# web_sch.net
KiCad netlist of a schematic drawn in Altium Designer
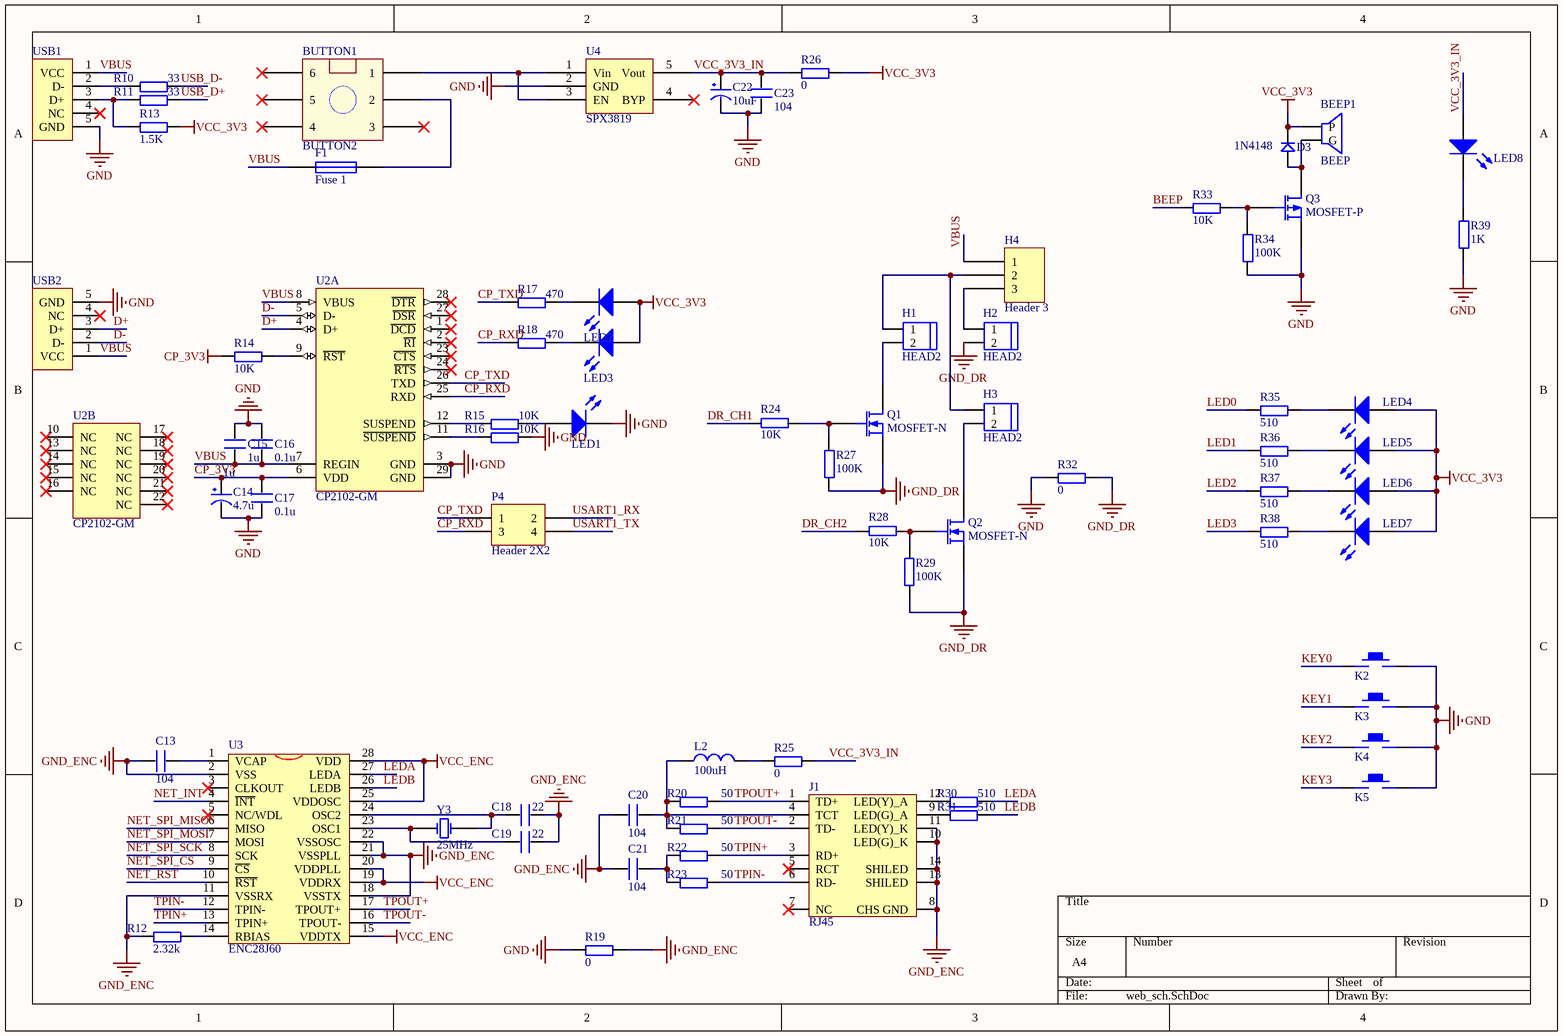
[diagram p0: web_sch.SchDoc]

(export (version "E")
  (design (tool "Eeschema 10.0.6"))
  (components
    (comp (ref "BEEP1") (value "BEEP") (footprint "BELL-5") (libsource (lib "MY_SCH_Lib") (part "BEEP")))
    (comp (ref "BUTTON1")
      (value "BUTTON2")
      (footprint "BTN8.5*8.5")
      (libsource (lib "MY_SCH_Lib") (part "BUTTON2"))
    )
    (comp (ref "C13") (value "104") (footprint "0603P") (libsource (lib "MY_SCH_Lib") (part "C")))
    (comp (ref "C14") (value "4.7u") (footprint "TAJ_A") (libsource (lib "MY_SCH_Lib") (part "CAP")))
    (comp (ref "C15")
      (value "1u")
      (footprint "0603P")
      (fields (field (name "ALTIUM_UNNAMED_1") "1u"))
      (libsource (lib "MY_SCH_Lib") (part "C"))
    )
    (comp (ref "C16") (value "0.1u") (footprint "0603P") (libsource (lib "MY_SCH_Lib") (part "C")))
    (comp (ref "C17") (value "0.1u") (footprint "0603P") (libsource (lib "MY_SCH_Lib") (part "C")))
    (comp (ref "C18") (value "22") (footprint "0603P") (libsource (lib "MY_SCH_Lib") (part "C")))
    (comp (ref "C19") (value "22") (footprint "0603P") (libsource (lib "MY_SCH_Lib") (part "C")))
    (comp (ref "C20") (value "104") (footprint "0603P") (libsource (lib "MY_SCH_Lib") (part "C")))
    (comp (ref "C21") (value "104") (footprint "0603P") (libsource (lib "MY_SCH_Lib") (part "C")))
    (comp (ref "C22") (value "10uF") (footprint "TAJ_A") (libsource (lib "MY_SCH_Lib") (part "CAP")))
    (comp (ref "C23") (value "104") (footprint "0603P") (libsource (lib "MY_SCH_Lib") (part "C")))
    (comp (ref "D3") (value "1N4148") (footprint "DIODE_SOP") (libsource (lib "MY_SCH_Lib") (part "D")))
    (comp (ref "F1")
      (value "Fuse 1")
      (footprint "0603P")
      (description "Fuse")
      (fields (field (name "PUBLISHER") "Altium Limited"))
      (libsource (lib "Miscellaneous Devices") (part "Fuse 1"))
    )
    (comp (ref "H1") (value "HEAD2") (footprint "HEAD2L-0.8") (libsource (lib "MY_SCH_Lib") (part "HEAD2")))
    (comp (ref "H2") (value "HEAD2") (footprint "HEAD2L-0.8") (libsource (lib "MY_SCH_Lib") (part "HEAD2")))
    (comp (ref "H3") (value "HEAD2") (footprint "HEAD2L-0.8") (libsource (lib "MY_SCH_Lib") (part "HEAD2")))
    (comp (ref "H4") (value "Header 3") (footprint "HEAD3") (libsource (lib "MY_SCH_Lib") (part "Header 3")))
    (comp (ref "J1") (value "RJ45") (footprint "RJ8-1") (libsource (lib "ENC28J60网络模块封装库") (part "HR911105")))
    (comp (ref "K2") (value "KEY") (footprint "KEY2") (libsource (lib "MY_SCH_Lib") (part "KEY")))
    (comp (ref "K3") (value "KEY") (footprint "KEY2") (libsource (lib "MY_SCH_Lib") (part "KEY")))
    (comp (ref "K4") (value "KEY") (footprint "KEY2") (libsource (lib "MY_SCH_Lib") (part "KEY")))
    (comp (ref "K5") (value "KEY") (footprint "KEY2") (libsource (lib "MY_SCH_Lib") (part "KEY")))
    (comp (ref "L2") (value "100uH") (footprint "0603P") (libsource (lib "MY_SCH_Lib") (part "Inductor")))
    (comp (ref "LED1")
      (value "LED")
      (footprint "LED_0603")
      (description "Typical RED, GREEN, YELLOW, AMBER GaAs LED")
      (fields (field (name "PUBLISHER") "Altium Limited"))
      (libsource (lib "MY_SCH_Lib") (part "LED"))
    )
    (comp (ref "LED2")
      (value "LED")
      (footprint "LED_0603")
      (description "Typical RED, GREEN, YELLOW, AMBER GaAs LED")
      (fields (field (name "PUBLISHER") "Altium Limited"))
      (libsource (lib "MY_SCH_Lib") (part "LED"))
    )
    (comp (ref "LED3")
      (value "LED")
      (footprint "LED_0603")
      (description "Typical RED, GREEN, YELLOW, AMBER GaAs LED")
      (fields (field (name "PUBLISHER") "Altium Limited"))
      (libsource (lib "MY_SCH_Lib") (part "LED"))
    )
    (comp (ref "LED4")
      (value "LED")
      (footprint "LED_0603")
      (description "Typical RED, GREEN, YELLOW, AMBER GaAs LED")
      (fields (field (name "PUBLISHER") "Altium Limited"))
      (libsource (lib "MY_SCH_Lib") (part "LED"))
    )
    (comp (ref "LED5")
      (value "LED")
      (footprint "LED_0603")
      (description "Typical RED, GREEN, YELLOW, AMBER GaAs LED")
      (fields (field (name "PUBLISHER") "Altium Limited"))
      (libsource (lib "MY_SCH_Lib") (part "LED"))
    )
    (comp (ref "LED6")
      (value "LED")
      (footprint "LED_0603")
      (description "Typical RED, GREEN, YELLOW, AMBER GaAs LED")
      (fields (field (name "PUBLISHER") "Altium Limited"))
      (libsource (lib "MY_SCH_Lib") (part "LED"))
    )
    (comp (ref "LED7")
      (value "LED")
      (footprint "LED_0603")
      (description "Typical RED, GREEN, YELLOW, AMBER GaAs LED")
      (fields (field (name "PUBLISHER") "Altium Limited"))
      (libsource (lib "MY_SCH_Lib") (part "LED"))
    )
    (comp (ref "LED8")
      (value "LED")
      (footprint "LED_0603")
      (description "Typical RED, GREEN, YELLOW, AMBER GaAs LED")
      (fields (field (name "PUBLISHER") "Altium Limited"))
      (libsource (lib "MY_SCH_Lib") (part "LED"))
    )
    (comp (ref "P4")
      (value "Header 2X2")
      (footprint "HDR2X2")
      (description "Header, 2-Pin, Dual row")
      (fields (field (name "PUBLISHER") "Altium Limited"))
      (libsource (lib "MY_SCH_Lib") (part "Header 2X2"))
    )
    (comp (ref "Q1")
      (value "MOSFET-N")
      (footprint "SOT-23")
      (description "N-Channel MOSFET")
      (fields (field (name "PUBLISHER") "Altium Limited"))
      (libsource (lib "MY_SCH_Lib") (part "MOSFET-N"))
    )
    (comp (ref "Q2")
      (value "MOSFET-N")
      (footprint "SOT-23")
      (description "N-Channel MOSFET")
      (fields (field (name "PUBLISHER") "Altium Limited"))
      (libsource (lib "MY_SCH_Lib") (part "MOSFET-N"))
    )
    (comp (ref "Q3")
      (value "MOSFET-P")
      (footprint "SOT-23")
      (description "P-Channel MOSFET")
      (fields (field (name "PUBLISHER") "Altium Limited"))
      (libsource (lib "MY_SCH_Lib") (part "MOSFET-P"))
    )
    (comp (ref "R10") (value "33") (footprint "0603P") (libsource (lib "MY_SCH_Lib") (part "R")))
    (comp (ref "R11") (value "33") (footprint "0603P") (libsource (lib "MY_SCH_Lib") (part "R")))
    (comp (ref "R12") (value "2.32k") (footprint "0603P") (libsource (lib "MY_SCH_Lib") (part "R")))
    (comp (ref "R13") (value "1.5K") (footprint "0603P") (libsource (lib "MY_SCH_Lib") (part "R")))
    (comp (ref "R14") (value "10K") (footprint "0603P") (libsource (lib "MY_SCH_Lib") (part "R")))
    (comp (ref "R15") (value "10K") (footprint "0603P") (libsource (lib "MY_SCH_Lib") (part "R")))
    (comp (ref "R16") (value "10K") (footprint "0603P") (libsource (lib "MY_SCH_Lib") (part "R")))
    (comp (ref "R17") (value "470") (footprint "0603P") (libsource (lib "MY_SCH_Lib") (part "R")))
    (comp (ref "R18") (value "470") (footprint "0603P") (libsource (lib "MY_SCH_Lib") (part "R")))
    (comp (ref "R19") (value "0") (footprint "0603P") (libsource (lib "MY_SCH_Lib") (part "R")))
    (comp (ref "R20") (value "50") (footprint "0603P") (libsource (lib "MY_SCH_Lib") (part "R")))
    (comp (ref "R21") (value "50") (footprint "0603P") (libsource (lib "MY_SCH_Lib") (part "R")))
    (comp (ref "R22") (value "50") (footprint "0603P") (libsource (lib "MY_SCH_Lib") (part "R")))
    (comp (ref "R23") (value "50") (footprint "0603P") (libsource (lib "MY_SCH_Lib") (part "R")))
    (comp (ref "R24") (value "10K") (footprint "0603P") (libsource (lib "MY_SCH_Lib") (part "R")))
    (comp (ref "R25") (value "0") (footprint "0603P") (libsource (lib "MY_SCH_Lib") (part "R")))
    (comp (ref "R26") (value "0") (footprint "0603P") (libsource (lib "MY_SCH_Lib") (part "R")))
    (comp (ref "R27") (value "100K") (footprint "0603P") (libsource (lib "MY_SCH_Lib") (part "R")))
    (comp (ref "R28") (value "10K") (footprint "0603P") (libsource (lib "MY_SCH_Lib") (part "R")))
    (comp (ref "R29") (value "100K") (footprint "0603P") (libsource (lib "MY_SCH_Lib") (part "R")))
    (comp (ref "R30") (value "510") (footprint "0603P") (libsource (lib "MY_SCH_Lib") (part "R")))
    (comp (ref "R31") (value "510") (footprint "0603P") (libsource (lib "MY_SCH_Lib") (part "R")))
    (comp (ref "R32") (value "0") (footprint "0603P") (libsource (lib "MY_SCH_Lib") (part "R")))
    (comp (ref "R33") (value "10K") (footprint "0603P") (libsource (lib "MY_SCH_Lib") (part "R")))
    (comp (ref "R34") (value "100K") (footprint "0603P") (libsource (lib "MY_SCH_Lib") (part "R")))
    (comp (ref "R35") (value "510") (footprint "0603P") (libsource (lib "MY_SCH_Lib") (part "R")))
    (comp (ref "R36") (value "510") (footprint "0603P") (libsource (lib "MY_SCH_Lib") (part "R")))
    (comp (ref "R37") (value "510") (footprint "0603P") (libsource (lib "MY_SCH_Lib") (part "R")))
    (comp (ref "R38") (value "510") (footprint "0603P") (libsource (lib "MY_SCH_Lib") (part "R")))
    (comp (ref "R39") (value "1K") (footprint "0603P") (libsource (lib "MY_SCH_Lib") (part "R")))
    (comp (ref "U2")
      (value "CP2102-GM")
      (footprint "SLAB-QFN-28-3125x3125TP_N")
      (description "Single-Chip USB to UART Bridge, 1024 Bytes EEPROM, -40 to 85 degC, 28-pin QFN, Tube")
      (fields (field (name "MANUFACTURER") "Silicon Labs"))
      (libsource (lib "Silicon Labs Interface") (part "CP2102-GM"))
    )
    (comp (ref "U3")
      (value "ENC28J60")
      (footprint "SSOP28")
      (libsource (lib "ENC28J60网络模块封装库") (part "ENC28J60"))
    )
    (comp (ref "U4") (value "SPX3819") (footprint "SOT23-5") (libsource (lib "MY_SCH_Lib") (part "SPX3819")))
    (comp (ref "USB1") (value "~") (footprint "USB-MICRO-5P-2") (libsource (lib "") (part "USB5_1")))
    (comp (ref "USB2") (value "~") (footprint "USB-MICRO-5P-2") (libsource (lib "MY_SCH_Lib") (part "USB5")))
    (comp (ref "Y3")
      (value "25MHz")
      (footprint "XTAL_US")
      (description "Crystal Oscillator")
      (fields (field (name "PUBLISHER") "Altium Limited"))
      (libsource (lib "MY_SCH_Lib") (part "XTAL"))
    )
  )
  (nets
    (net (code "1") (name "/BEEP") (class "Default") (node (ref "R33") (pin "1") (pintype "passive")))
    (net (code "2") (name "/CP_RXD") (class "Default")
      (node (ref "P4") (pin "3") (pinfunction "3_3") (pintype "passive"))
      (node (ref "R18") (pin "1") (pintype "passive"))
      (node (ref "U2") (pin "25") (pinfunction "RXD_25") (pintype "input"))
    )
    (net (code "3") (name "/CP_TXD") (class "Default")
      (node (ref "P4") (pin "1") (pinfunction "1_1") (pintype "passive"))
      (node (ref "R17") (pin "1") (pintype "passive"))
      (node (ref "U2") (pin "26") (pinfunction "TXD_26") (pintype "output"))
    )
    (net (code "4") (name "/D+") (class "Default")
      (node (ref "U2") (pin "4") (pinfunction "D+_4") (pintype "bidirectional"))
      (node (ref "USB2") (pin "3") (pinfunction "D+_3") (pintype "passive"))
    )
    (net (code "5") (name "/D-") (class "Default")
      (node (ref "U2") (pin "5") (pinfunction "D-_5") (pintype "bidirectional"))
      (node (ref "USB2") (pin "2") (pinfunction "D-_2") (pintype "passive"))
    )
    (net (code "6") (name "/DR_CH1") (class "Default") (node (ref "R24") (pin "2") (pintype "passive")))
    (net (code "7") (name "/DR_CH2") (class "Default") (node (ref "R28") (pin "2") (pintype "passive")))
    (net (code "8") (name "/KEY0") (class "Default")
      (node (ref "K2") (pin "1") (pinfunction "1_1") (pintype "passive"))
    )
    (net (code "9") (name "/KEY1") (class "Default")
      (node (ref "K3") (pin "1") (pinfunction "1_1") (pintype "passive"))
    )
    (net (code "10") (name "/KEY2") (class "Default")
      (node (ref "K4") (pin "1") (pinfunction "1_1") (pintype "passive"))
    )
    (net (code "11") (name "/KEY3") (class "Default")
      (node (ref "K5") (pin "1") (pinfunction "1_1") (pintype "passive"))
    )
    (net (code "12") (name "/LED0") (class "Default") (node (ref "R35") (pin "1") (pintype "passive")))
    (net (code "13") (name "/LED1") (class "Default") (node (ref "R36") (pin "1") (pintype "passive")))
    (net (code "14") (name "/LED2") (class "Default") (node (ref "R37") (pin "1") (pintype "passive")))
    (net (code "15") (name "/LED3") (class "Default") (node (ref "R38") (pin "1") (pintype "passive")))
    (net (code "16") (name "/LEDA") (class "Default")
      (node (ref "R30") (pin "2") (pintype "passive"))
      (node (ref "U3") (pin "27") (pinfunction "LEDA_27") (pintype "passive"))
    )
    (net (code "17") (name "/LEDB") (class "Default")
      (node (ref "R31") (pin "2") (pintype "passive"))
      (node (ref "U3") (pin "26") (pinfunction "LEDB_26") (pintype "passive"))
    )
    (net (code "18") (name "/NET_INT") (class "Default")
      (node (ref "U3") (pin "4") (pinfunction "~{INT}_4") (pintype "passive"))
    )
    (net (code "19") (name "/NET_RST") (class "Default")
      (node (ref "U3") (pin "10") (pinfunction "~{RST}_10") (pintype "passive"))
    )
    (net (code "20") (name "/NET_SPI_CS") (class "Default")
      (node (ref "U3") (pin "9") (pinfunction "~{CS}_9") (pintype "passive"))
    )
    (net (code "21") (name "/NET_SPI_MISO") (class "Default")
      (node (ref "U3") (pin "6") (pinfunction "MISO_6") (pintype "passive"))
    )
    (net (code "22") (name "/NET_SPI_MOSI") (class "Default")
      (node (ref "U3") (pin "7") (pinfunction "MOSI_7") (pintype "passive"))
    )
    (net (code "23") (name "/NET_SPI_SCK") (class "Default")
      (node (ref "U3") (pin "8") (pinfunction "SCK_8") (pintype "passive"))
    )
    (net (code "24") (name "/TPIN+") (class "Default")
      (node (ref "J1") (pin "3") (pinfunction "RD+_3") (pintype "passive"))
      (node (ref "R22") (pin "2") (pintype "passive"))
      (node (ref "U3") (pin "13") (pinfunction "TPIN+_13") (pintype "passive"))
    )
    (net (code "25") (name "/TPIN-") (class "Default")
      (node (ref "J1") (pin "6") (pinfunction "RD-_6") (pintype "passive"))
      (node (ref "R23") (pin "2") (pintype "passive"))
      (node (ref "U3") (pin "12") (pinfunction "TPIN-_12") (pintype "passive"))
    )
    (net (code "26") (name "/TPOUT+") (class "Default")
      (node (ref "J1") (pin "1") (pinfunction "TD+_1") (pintype "passive"))
      (node (ref "R20") (pin "2") (pintype "passive"))
      (node (ref "U3") (pin "17") (pinfunction "TPOUT+_17") (pintype "passive"))
    )
    (net (code "27") (name "/TPOUT-") (class "Default")
      (node (ref "J1") (pin "2") (pinfunction "TD-_2") (pintype "passive"))
      (node (ref "R21") (pin "2") (pintype "passive"))
      (node (ref "U3") (pin "16") (pinfunction "TPOUT-_16") (pintype "passive"))
    )
    (net (code "28") (name "/USART1_RX") (class "Default")
      (node (ref "P4") (pin "2") (pinfunction "2_2") (pintype "passive"))
    )
    (net (code "29") (name "/USART1_TX") (class "Default")
      (node (ref "P4") (pin "4") (pinfunction "4_4") (pintype "passive"))
    )
    (net (code "30") (name "/USB_D+") (class "Default") (node (ref "R11") (pin "2") (pintype "passive")))
    (net (code "31") (name "/USB_D-") (class "Default") (node (ref "R10") (pin "2") (pintype "passive")))
    (net (code "32") (name "/VBUS") (class "Default")
      (node (ref "C15") (pin "1") (pintype "passive"))
      (node (ref "C16") (pin "1") (pintype "passive"))
      (node (ref "F1") (pin "1") (pinfunction "1_1") (pintype "passive"))
      (node (ref "H4") (pin "1") (pinfunction "1_1") (pintype "passive"))
      (node (ref "U2") (pin "7") (pinfunction "REGIN_7") (pintype "power_in"))
      (node (ref "U2") (pin "8") (pinfunction "VBUS_8") (pintype "input"))
      (node (ref "USB1") (pin "1") (pinfunction "VCC_1") (pintype "passive"))
      (node (ref "USB2") (pin "1") (pinfunction "VCC_1") (pintype "passive"))
    )
    (net (code "33") (name "/VCC_3V3_IN") (class "Default")
      (node (ref "C22") (pin "1") (pinfunction "VCC_1") (pintype "passive"))
      (node (ref "C23") (pin "2") (pintype "passive"))
      (node (ref "LED8") (pin "1") (pinfunction "A_1") (pintype "passive"))
      (node (ref "R25") (pin "2") (pintype "passive"))
      (node (ref "R26") (pin "1") (pintype "passive"))
      (node (ref "U4") (pin "5") (pinfunction "Vout_5") (pintype "passive"))
    )
    (net (code "34") (name "CP_3V3") (class "Default")
      (node (ref "C14") (pin "1") (pinfunction "VCC_1") (pintype "passive"))
      (node (ref "C17") (pin "2") (pintype "passive"))
      (node (ref "R14") (pin "1") (pintype "passive"))
      (node (ref "U2") (pin "6") (pinfunction "VDD_6") (pintype "power_in"))
    )
    (net (code "35") (name "GND") (class "Default")
      (node (ref "C14") (pin "2") (pinfunction "GND_2") (pintype "passive"))
      (node (ref "C15") (pin "2") (pintype "passive"))
      (node (ref "C16") (pin "2") (pintype "passive"))
      (node (ref "C17") (pin "1") (pintype "passive"))
      (node (ref "C22") (pin "2") (pinfunction "GND_2") (pintype "passive"))
      (node (ref "C23") (pin "1") (pintype "passive"))
      (node (ref "K2") (pin "2") (pinfunction "2_2") (pintype "passive"))
      (node (ref "K3") (pin "2") (pinfunction "2_2") (pintype "passive"))
      (node (ref "K4") (pin "2") (pinfunction "2_2") (pintype "passive"))
      (node (ref "K5") (pin "2") (pinfunction "2_2") (pintype "passive"))
      (node (ref "LED1") (pin "2") (pinfunction "K_2") (pintype "passive"))
      (node (ref "Q3") (pin "2") (pinfunction "S_2") (pintype "passive"))
      (node (ref "R16") (pin "2") (pintype "passive"))
      (node (ref "R19") (pin "1") (pintype "passive"))
      (node (ref "R32") (pin "1") (pintype "passive"))
      (node (ref "R34") (pin "1") (pintype "passive"))
      (node (ref "R39") (pin "1") (pintype "passive"))
      (node (ref "U2") (pin "29") (pinfunction "GND_29") (pintype "power_in"))
      (node (ref "U2") (pin "3") (pinfunction "GND_3") (pintype "power_in"))
      (node (ref "U4") (pin "2") (pinfunction "GND_2") (pintype "passive"))
      (node (ref "USB1") (pin "5") (pinfunction "GND_5") (pintype "passive"))
      (node (ref "USB2") (pin "5") (pinfunction "GND_5") (pintype "passive"))
    )
    (net (code "36") (name "GND_DR") (class "Default")
      (node (ref "H2") (pin "2") (pinfunction "2_2") (pintype "passive"))
      (node (ref "Q1") (pin "2") (pinfunction "S_2") (pintype "passive"))
      (node (ref "Q2") (pin "2") (pinfunction "S_2") (pintype "passive"))
      (node (ref "R27") (pin "1") (pintype "passive"))
      (node (ref "R29") (pin "2") (pintype "passive"))
      (node (ref "R32") (pin "2") (pintype "passive"))
    )
    (net (code "37") (name "GND_ENC") (class "Default")
      (node (ref "C13") (pin "1") (pintype "passive"))
      (node (ref "C18") (pin "2") (pintype "passive"))
      (node (ref "C19") (pin "2") (pintype "passive"))
      (node (ref "C20") (pin "1") (pintype "passive"))
      (node (ref "C21") (pin "1") (pintype "passive"))
      (node (ref "J1") (pin "10") (pinfunction "LED(G)_K_10") (pintype "passive"))
      (node (ref "J1") (pin "11") (pinfunction "LED(Y)_K_11") (pintype "passive"))
      (node (ref "J1") (pin "13") (pinfunction "SHILED_13") (pintype "passive"))
      (node (ref "J1") (pin "14") (pinfunction "SHILED_14") (pintype "passive"))
      (node (ref "J1") (pin "8") (pinfunction "CHS_GND_8") (pintype "passive"))
      (node (ref "R12") (pin "1") (pintype "passive"))
      (node (ref "R19") (pin "2") (pintype "passive"))
      (node (ref "U3") (pin "11") (pinfunction "VSSRX_11") (pintype "passive"))
      (node (ref "U3") (pin "18") (pinfunction "VSSTX_18") (pintype "passive"))
      (node (ref "U3") (pin "2") (pinfunction "VSS_2") (pintype "passive"))
      (node (ref "U3") (pin "21") (pinfunction "VSSPLL_21") (pintype "passive"))
      (node (ref "U3") (pin "22") (pinfunction "VSSOSC_22") (pintype "passive"))
    )
    (net (code "38") (name "Net-(BEEP1-G)") (class "Default")
      (node (ref "BEEP1") (pin "2") (pinfunction "G_2") (pintype "passive"))
      (node (ref "D3") (pin "1") (pintype "passive"))
      (node (ref "Q3") (pin "3") (pinfunction "D_3") (pintype "passive"))
    )
    (net (code "39") (name "Net-(BUTTON1-Pad2)") (class "Default")
      (node (ref "BUTTON1") (pin "2") (pinfunction "2_2") (pintype "passive"))
      (node (ref "F1") (pin "2") (pinfunction "2_2") (pintype "passive"))
    )
    (net (code "40") (name "Net-(C21-Pad2)") (class "Default")
      (node (ref "C21") (pin "2") (pintype "passive"))
      (node (ref "R22") (pin "1") (pintype "passive"))
      (node (ref "R23") (pin "1") (pintype "passive"))
    )
    (net (code "41") (name "Net-(H1-Pad1)") (class "Default")
      (node (ref "H1") (pin "1") (pinfunction "1_1") (pintype "passive"))
      (node (ref "H3") (pin "1") (pinfunction "1_1") (pintype "passive"))
      (node (ref "H4") (pin "2") (pinfunction "2_2") (pintype "passive"))
    )
    (net (code "42") (name "Net-(H2-Pad1)") (class "Default")
      (node (ref "H2") (pin "1") (pinfunction "1_1") (pintype "passive"))
      (node (ref "H4") (pin "3") (pinfunction "3_3") (pintype "passive"))
    )
    (net (code "43") (name "Net-(J1-LED(G)_A)") (class "Default")
      (node (ref "J1") (pin "9") (pinfunction "LED(G)_A_9") (pintype "passive"))
      (node (ref "R31") (pin "1") (pintype "passive"))
    )
    (net (code "44") (name "Net-(J1-LED(Y)_A)") (class "Default")
      (node (ref "J1") (pin "12") (pinfunction "LED(Y)_A_12") (pintype "passive"))
      (node (ref "R30") (pin "1") (pintype "passive"))
    )
    (net (code "45") (name "Net-(J1-TCT)") (class "Default")
      (node (ref "C20") (pin "2") (pintype "passive"))
      (node (ref "J1") (pin "4") (pinfunction "TCT_4") (pintype "passive"))
      (node (ref "L2") (pin "1") (pinfunction "1_1") (pintype "passive"))
      (node (ref "R20") (pin "1") (pintype "passive"))
      (node (ref "R21") (pin "1") (pintype "passive"))
    )
    (net (code "46") (name "Net-(L2-Pad2)") (class "Default")
      (node (ref "L2") (pin "2") (pinfunction "2_2") (pintype "passive"))
      (node (ref "R25") (pin "1") (pintype "passive"))
    )
    (net (code "47") (name "Net-(LED1-A)") (class "Default")
      (node (ref "LED1") (pin "1") (pinfunction "A_1") (pintype "passive"))
      (node (ref "R15") (pin "2") (pintype "passive"))
    )
    (net (code "48") (name "Net-(LED2-K)") (class "Default")
      (node (ref "LED2") (pin "2") (pinfunction "K_2") (pintype "passive"))
      (node (ref "R17") (pin "2") (pintype "passive"))
    )
    (net (code "49") (name "Net-(LED3-K)") (class "Default")
      (node (ref "LED3") (pin "2") (pinfunction "K_2") (pintype "passive"))
      (node (ref "R18") (pin "2") (pintype "passive"))
    )
    (net (code "50") (name "Net-(LED4-K)") (class "Default")
      (node (ref "LED4") (pin "2") (pinfunction "K_2") (pintype "passive"))
      (node (ref "R35") (pin "2") (pintype "passive"))
    )
    (net (code "51") (name "Net-(LED5-K)") (class "Default")
      (node (ref "LED5") (pin "2") (pinfunction "K_2") (pintype "passive"))
      (node (ref "R36") (pin "2") (pintype "passive"))
    )
    (net (code "52") (name "Net-(LED6-K)") (class "Default")
      (node (ref "LED6") (pin "2") (pinfunction "K_2") (pintype "passive"))
      (node (ref "R37") (pin "2") (pintype "passive"))
    )
    (net (code "53") (name "Net-(LED7-K)") (class "Default")
      (node (ref "LED7") (pin "2") (pinfunction "K_2") (pintype "passive"))
      (node (ref "R38") (pin "2") (pintype "passive"))
    )
    (net (code "54") (name "Net-(LED8-K)") (class "Default")
      (node (ref "LED8") (pin "2") (pinfunction "K_2") (pintype "passive"))
      (node (ref "R39") (pin "2") (pintype "passive"))
    )
    (net (code "55") (name "Net-(Q1-D)") (class "Default")
      (node (ref "H1") (pin "2") (pinfunction "2_2") (pintype "passive"))
      (node (ref "Q1") (pin "3") (pinfunction "D_3") (pintype "passive"))
    )
    (net (code "56") (name "Net-(Q1-G)") (class "Default")
      (node (ref "Q1") (pin "1") (pinfunction "G_1") (pintype "passive"))
      (node (ref "R24") (pin "1") (pintype "passive"))
      (node (ref "R27") (pin "2") (pintype "passive"))
    )
    (net (code "57") (name "Net-(Q2-D)") (class "Default")
      (node (ref "H3") (pin "2") (pinfunction "2_2") (pintype "passive"))
      (node (ref "Q2") (pin "3") (pinfunction "D_3") (pintype "passive"))
    )
    (net (code "58") (name "Net-(Q2-G)") (class "Default")
      (node (ref "Q2") (pin "1") (pinfunction "G_1") (pintype "passive"))
      (node (ref "R28") (pin "1") (pintype "passive"))
      (node (ref "R29") (pin "1") (pintype "passive"))
    )
    (net (code "59") (name "Net-(Q3-G)") (class "Default")
      (node (ref "Q3") (pin "1") (pinfunction "G_1") (pintype "passive"))
      (node (ref "R33") (pin "2") (pintype "passive"))
      (node (ref "R34") (pin "2") (pintype "passive"))
    )
    (net (code "60") (name "Net-(U2A-SUSPEND)") (class "Default")
      (node (ref "R15") (pin "1") (pintype "passive"))
      (node (ref "U2") (pin "12") (pinfunction "SUSPEND_12") (pintype "output"))
    )
    (net (code "61") (name "Net-(U2A-~{RST})") (class "Default")
      (node (ref "R14") (pin "2") (pintype "passive"))
      (node (ref "U2") (pin "9") (pinfunction "~{RST}_9") (pintype "bidirectional"))
    )
    (net (code "62") (name "Net-(U2A-~{SUSPEND})") (class "Default")
      (node (ref "R16") (pin "1") (pintype "passive"))
      (node (ref "U2") (pin "11") (pinfunction "~{SUSPEND}_11") (pintype "output"))
    )
    (net (code "63") (name "Net-(U3-OSC1)") (class "Default")
      (node (ref "C19") (pin "1") (pintype "passive"))
      (node (ref "U3") (pin "23") (pinfunction "OSC1_23") (pintype "passive"))
      (node (ref "Y3") (pin "1") (pinfunction "OSC1_1") (pintype "passive"))
    )
    (net (code "64") (name "Net-(U3-OSC2)") (class "Default")
      (node (ref "C18") (pin "1") (pintype "passive"))
      (node (ref "U3") (pin "24") (pinfunction "OSC2_24") (pintype "passive"))
      (node (ref "Y3") (pin "2") (pinfunction "OSC2_2") (pintype "passive"))
    )
    (net (code "65") (name "Net-(U3-RBIAS)") (class "Default")
      (node (ref "R12") (pin "2") (pintype "passive"))
      (node (ref "U3") (pin "14") (pinfunction "RBIAS_14") (pintype "passive"))
    )
    (net (code "66") (name "Net-(U3-VCAP)") (class "Default")
      (node (ref "C13") (pin "2") (pintype "passive"))
      (node (ref "U3") (pin "1") (pinfunction "VCAP_1") (pintype "passive"))
    )
    (net (code "67") (name "Net-(U4-EN)") (class "Default")
      (node (ref "BUTTON1") (pin "1") (pinfunction "1_1") (pintype "passive"))
      (node (ref "U4") (pin "1") (pinfunction "Vin_1") (pintype "passive"))
      (node (ref "U4") (pin "3") (pinfunction "EN_3") (pintype "passive"))
    )
    (net (code "68") (name "Net-(USB1-D+)") (class "Default")
      (node (ref "R11") (pin "1") (pintype "passive"))
      (node (ref "R13") (pin "1") (pintype "passive"))
      (node (ref "USB1") (pin "3") (pinfunction "D+_3") (pintype "passive"))
    )
    (net (code "69") (name "Net-(USB1-D-)") (class "Default")
      (node (ref "R10") (pin "1") (pintype "passive"))
      (node (ref "USB1") (pin "2") (pinfunction "D-_2") (pintype "passive"))
    )
    (net (code "70") (name "VCC_3V3") (class "Default")
      (node (ref "BEEP1") (pin "1") (pinfunction "P_1") (pintype "passive"))
      (node (ref "D3") (pin "2") (pintype "passive"))
      (node (ref "LED2") (pin "1") (pinfunction "A_1") (pintype "passive"))
      (node (ref "LED3") (pin "1") (pinfunction "A_1") (pintype "passive"))
      (node (ref "LED4") (pin "1") (pinfunction "A_1") (pintype "passive"))
      (node (ref "LED5") (pin "1") (pinfunction "A_1") (pintype "passive"))
      (node (ref "LED6") (pin "1") (pinfunction "A_1") (pintype "passive"))
      (node (ref "LED7") (pin "1") (pinfunction "A_1") (pintype "passive"))
      (node (ref "R13") (pin "2") (pintype "passive"))
      (node (ref "R26") (pin "2") (pintype "passive"))
    )
    (net (code "71") (name "VCC_ENC") (class "Default")
      (node (ref "U3") (pin "15") (pinfunction "VDDTX_15") (pintype "passive"))
      (node (ref "U3") (pin "19") (pinfunction "VDDRX_19") (pintype "passive"))
      (node (ref "U3") (pin "20") (pinfunction "VDDPLL_20") (pintype "passive"))
      (node (ref "U3") (pin "25") (pinfunction "VDDOSC_25") (pintype "passive"))
      (node (ref "U3") (pin "28") (pinfunction "VDD_28") (pintype "passive"))
    )
    (net (code "72") (name "unconnected-(BUTTON1-Pad3)") (class "Default")
      (node (ref "BUTTON1") (pin "3") (pinfunction "3_3") (pintype "passive+no_connect"))
    )
    (net (code "73") (name "unconnected-(BUTTON1-Pad4)") (class "Default")
      (node (ref "BUTTON1") (pin "4") (pinfunction "4_4") (pintype "passive+no_connect"))
    )
    (net (code "74") (name "unconnected-(BUTTON1-Pad5)") (class "Default")
      (node (ref "BUTTON1") (pin "5") (pinfunction "5_5") (pintype "passive+no_connect"))
    )
    (net (code "75") (name "unconnected-(BUTTON1-Pad6)") (class "Default")
      (node (ref "BUTTON1") (pin "6") (pinfunction "6_6") (pintype "passive+no_connect"))
    )
    (net (code "76") (name "unconnected-(J1-NC-Pad7)") (class "Default")
      (node (ref "J1") (pin "7") (pinfunction "NC_7") (pintype "passive+no_connect"))
    )
    (net (code "77") (name "unconnected-(J1-RCT-Pad5)") (class "Default")
      (node (ref "J1") (pin "5") (pinfunction "RCT_5") (pintype "passive+no_connect"))
    )
    (net (code "78") (name "unconnected-(U2A-~{CTS}-Pad23)") (class "Default")
      (node (ref "U2") (pin "23") (pinfunction "~{CTS}_23") (pintype "input+no_connect"))
    )
    (net (code "79") (name "unconnected-(U2A-~{DCD}-Pad1)") (class "Default")
      (node (ref "U2") (pin "1") (pinfunction "~{DCD}_1") (pintype "input+no_connect"))
    )
    (net (code "80") (name "unconnected-(U2A-~{DSR}-Pad27)") (class "Default")
      (node (ref "U2") (pin "27") (pinfunction "~{DSR}_27") (pintype "input+no_connect"))
    )
    (net (code "81") (name "unconnected-(U2A-~{DTR}-Pad28)") (class "Default")
      (node (ref "U2") (pin "28") (pinfunction "~{DTR}_28") (pintype "output+no_connect"))
    )
    (net (code "82") (name "unconnected-(U2A-~{RI}-Pad2)") (class "Default")
      (node (ref "U2") (pin "2") (pinfunction "~{RI}_2") (pintype "input+no_connect"))
    )
    (net (code "83") (name "unconnected-(U2A-~{RTS}-Pad24)") (class "Default")
      (node (ref "U2") (pin "24") (pinfunction "~{RTS}_24") (pintype "output+no_connect"))
    )
    (net (code "84") (name "unconnected-(U2B-NC-Pad10)") (class "Default")
      (node (ref "U2") (pin "10") (pinfunction "NC_10") (pintype "passive+no_connect"))
    )
    (net (code "85") (name "unconnected-(U2B-NC-Pad13)") (class "Default")
      (node (ref "U2") (pin "13") (pinfunction "NC_13") (pintype "passive+no_connect"))
    )
    (net (code "86") (name "unconnected-(U2B-NC-Pad14)") (class "Default")
      (node (ref "U2") (pin "14") (pinfunction "NC_14") (pintype "passive+no_connect"))
    )
    (net (code "87") (name "unconnected-(U2B-NC-Pad15)") (class "Default")
      (node (ref "U2") (pin "15") (pinfunction "NC_15") (pintype "passive+no_connect"))
    )
    (net (code "88") (name "unconnected-(U2B-NC-Pad16)") (class "Default")
      (node (ref "U2") (pin "16") (pinfunction "NC_16") (pintype "passive+no_connect"))
    )
    (net (code "89") (name "unconnected-(U2B-NC-Pad17)") (class "Default")
      (node (ref "U2") (pin "17") (pinfunction "NC_17") (pintype "passive+no_connect"))
    )
    (net (code "90") (name "unconnected-(U2B-NC-Pad18)") (class "Default")
      (node (ref "U2") (pin "18") (pinfunction "NC_18") (pintype "passive+no_connect"))
    )
    (net (code "91") (name "unconnected-(U2B-NC-Pad19)") (class "Default")
      (node (ref "U2") (pin "19") (pinfunction "NC_19") (pintype "passive+no_connect"))
    )
    (net (code "92") (name "unconnected-(U2B-NC-Pad20)") (class "Default")
      (node (ref "U2") (pin "20") (pinfunction "NC_20") (pintype "passive+no_connect"))
    )
    (net (code "93") (name "unconnected-(U2B-NC-Pad21)") (class "Default")
      (node (ref "U2") (pin "21") (pinfunction "NC_21") (pintype "passive+no_connect"))
    )
    (net (code "94") (name "unconnected-(U2B-NC-Pad22)") (class "Default")
      (node (ref "U2") (pin "22") (pinfunction "NC_22") (pintype "passive+no_connect"))
    )
    (net (code "95") (name "unconnected-(U3-CLKOUT-Pad3)") (class "Default")
      (node (ref "U3") (pin "3") (pinfunction "CLKOUT_3") (pintype "passive+no_connect"))
    )
    (net (code "96") (name "unconnected-(U3-NC{slash}WDL-Pad5)") (class "Default")
      (node (ref "U3") (pin "5") (pinfunction "NC/WDL_5") (pintype "passive+no_connect"))
    )
    (net (code "97") (name "unconnected-(U4-BYP-Pad4)") (class "Default")
      (node (ref "U4") (pin "4") (pinfunction "BYP_4") (pintype "passive+no_connect"))
    )
    (net (code "98") (name "unconnected-(USB1-NC-Pad4)") (class "Default")
      (node (ref "USB1") (pin "4") (pinfunction "NC_4") (pintype "passive+no_connect"))
    )
    (net (code "99") (name "unconnected-(USB2-NC-Pad4)") (class "Default")
      (node (ref "USB2") (pin "4") (pinfunction "NC_4") (pintype "passive+no_connect"))
    )
  )
)
